# barbarov_guc_dagitim_karti.net
KiCad netlist of a schematic drawn in Altium Designer
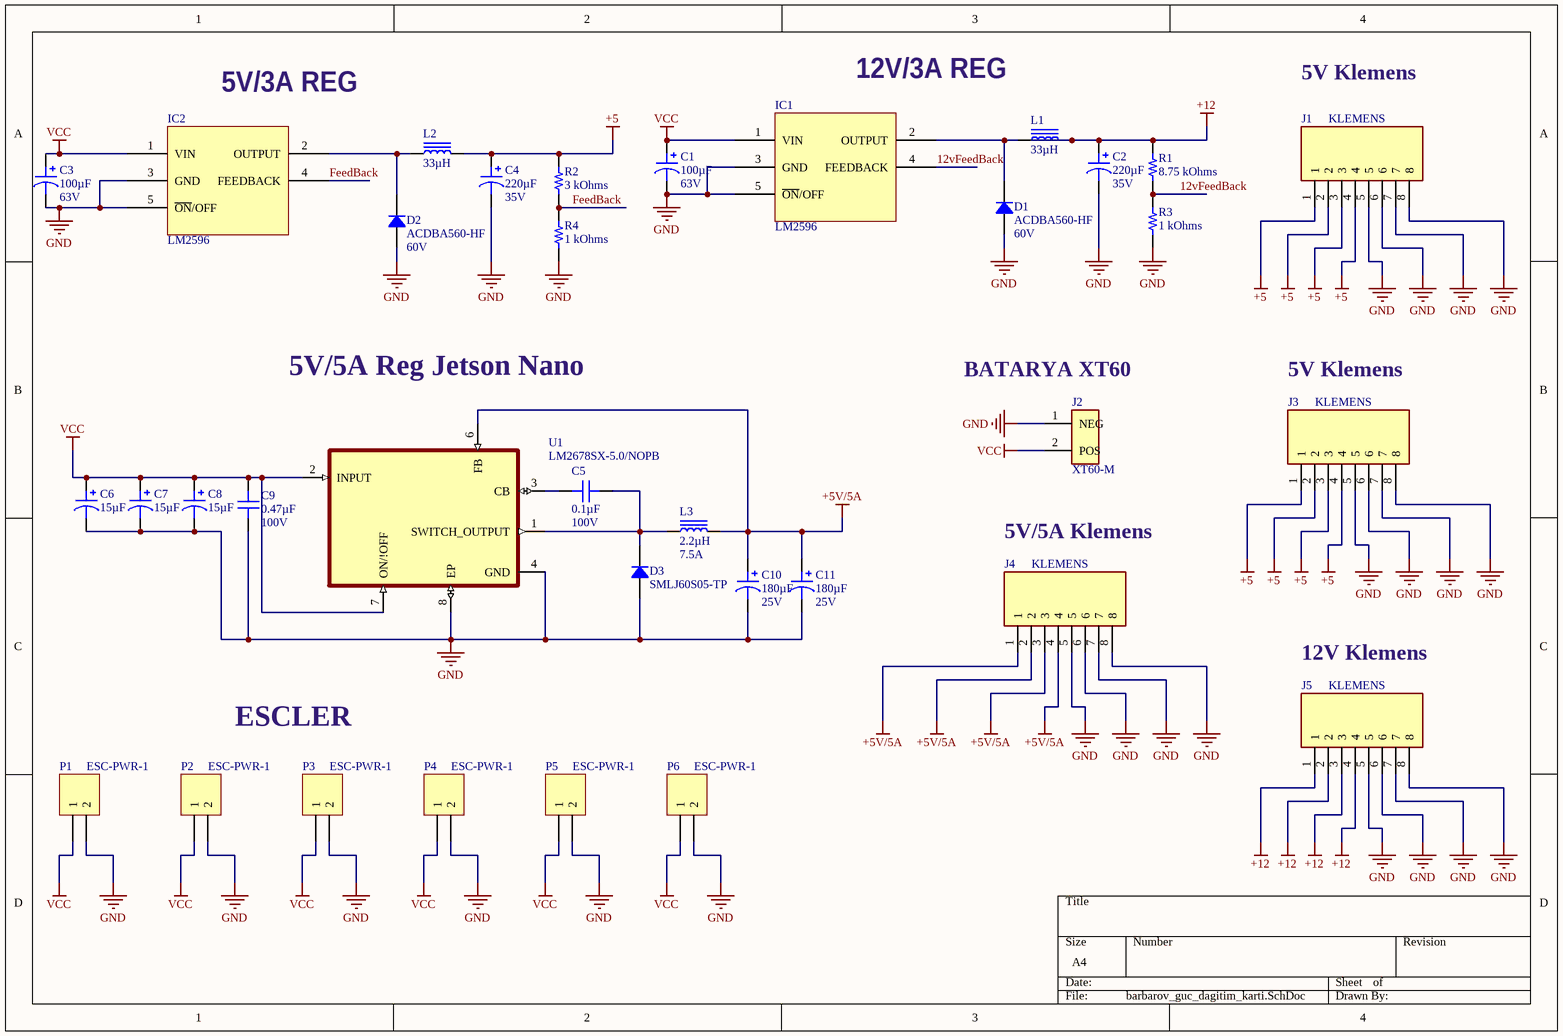
[diagram p0: barbarov_guc_dagitim_karti.SchDoc]

(export (version "E")
  (design (tool "Eeschema 10.0.6"))
  (components
    (comp (ref "C1")
      (value "100µF")
      (footprint "CAP TH ALUM ELEC D8.00mm S3.50mm H12.50mm")
      (description "CAP ALUM 100UF 20% 63V RADIAL")
      (fields
        (field (name "PART NUMBER") "ECA-1JM101")
        (field (name "MANUFACTURER") "Panasonic Electronic Components")
        (field (name "VOLTAGE - RATED") "63V")
      )
      (libsource (lib "Celestial Altium Library - altium_library") (part "Polarised Capacitor"))
    )
    (comp (ref "C2")
      (value "220µF")
      (footprint "CAP TH ALUM ELEC D8.00mm S3.50mm H12.50mm")
      (description "CAP ALUM 220UF 20% 35V RADIAL")
      (fields
        (field (name "PART NUMBER") "ECA-1VM221")
        (field (name "MANUFACTURER") "Panasonic Electronic Components")
        (field (name "VOLTAGE - RATED") "35V")
      )
      (libsource (lib "Celestial Altium Library - altium_library") (part "Polarised Capacitor"))
    )
    (comp (ref "C3")
      (value "100µF")
      (footprint "CAP TH ALUM ELEC D8.00mm S3.50mm H12.50mm")
      (description "CAP ALUM 100UF 20% 63V RADIAL")
      (fields
        (field (name "PART NUMBER") "ECA-1JM101")
        (field (name "MANUFACTURER") "Panasonic Electronic Components")
        (field (name "VOLTAGE - RATED") "63V")
      )
      (libsource (lib "Celestial Altium Library - altium_library") (part "Polarised Capacitor"))
    )
    (comp (ref "C4")
      (value "220µF")
      (footprint "CAP TH ALUM ELEC D8.00mm S3.50mm H12.50mm")
      (description "CAP ALUM 220UF 20% 35V RADIAL")
      (fields
        (field (name "PART NUMBER") "ECA-1VM221")
        (field (name "MANUFACTURER") "Panasonic Electronic Components")
        (field (name "VOLTAGE - RATED") "35V")
      )
      (libsource (lib "Celestial Altium Library - altium_library") (part "Polarised Capacitor"))
    )
    (comp (ref "C5")
      (value "0.1µF")
      (footprint "CAP 1206_3216 - 1.8MM")
      (description "CAP CER 0.47UF 100V X7R 1206")
      (fields
        (field (name "PART NUMBER") "C3216X7R2A474K160AE")
        (field (name "MANUFACTURER") "TDK Corporation")
        (field (name "VOLTAGE - RATED") "100V")
      )
      (libsource (lib "Celestial Altium Library - altium_library") (part "Capacitor"))
    )
    (comp (ref "C6")
      (value "15µF")
      (footprint "CAP TH ALUM ELEC D8.00mm S3.50mm H11.50mm")
      (description "CAP ALUM 15UF 20% 100V RADIAL")
      (fields (field (name "PART NUMBER") "UPW2A150MPD") (field (name "MANUFACTURER") "Nichicon"))
      (libsource (lib "Celestial Altium Library - altium_library") (part "Polarised Capacitor"))
    )
    (comp (ref "C7")
      (value "15µF")
      (footprint "CAP TH ALUM ELEC D8.00mm S3.50mm H11.50mm")
      (description "CAP ALUM 15UF 20% 100V RADIAL")
      (fields (field (name "PART NUMBER") "UPW2A150MPD") (field (name "MANUFACTURER") "Nichicon"))
      (libsource (lib "Celestial Altium Library - altium_library") (part "Polarised Capacitor"))
    )
    (comp (ref "C8")
      (value "15µF")
      (footprint "CAP TH ALUM ELEC D8.00mm S3.50mm H11.50mm")
      (description "CAP ALUM 15UF 20% 100V RADIAL")
      (fields (field (name "PART NUMBER") "UPW2A150MPD") (field (name "MANUFACTURER") "Nichicon"))
      (libsource (lib "Celestial Altium Library - altium_library") (part "Polarised Capacitor"))
    )
    (comp (ref "C9")
      (value "0.47µF")
      (footprint "CAP 1206_3216 - 1.8MM")
      (description "CAP CER 0.47UF 100V X7R 1206")
      (fields
        (field (name "PART NUMBER") "C3216X7R2A474K160AE")
        (field (name "MANUFACTURER") "TDK Corporation")
        (field (name "VOLTAGE - RATED") "100V")
      )
      (libsource (lib "Celestial Altium Library - altium_library") (part "Capacitor"))
    )
    (comp (ref "C10")
      (value "180µF")
      (footprint "CAP TH ALUM ELEC D8.00mm S3.50mm H13.00mm")
      (description "CAP ALUM 180UF 20% 25V THRU HOLE")
      (fields
        (field (name "PART NUMBER") "860080474009")
        (field (name "MANUFACTURER") "Würth Elektronik")
        (field (name "VOLTAGE - RATED") "25V")
      )
      (libsource (lib "Celestial Altium Library - altium_library") (part "Polarised Capacitor"))
    )
    (comp (ref "C11")
      (value "180µF")
      (footprint "CAP TH ALUM ELEC D8.00mm S3.50mm H13.00mm")
      (description "CAP ALUM 180UF 20% 25V THRU HOLE")
      (fields
        (field (name "PART NUMBER") "860080474009")
        (field (name "MANUFACTURER") "Würth Elektronik")
        (field (name "VOLTAGE - RATED") "25V")
      )
      (libsource (lib "Celestial Altium Library - altium_library") (part "Polarised Capacitor"))
    )
    (comp (ref "D1")
      (value "ACDBA560-HF")
      (footprint "DO214AC SMA")
      (description "DIODE SCHOTTKY 60V 5A DO214AC")
      (fields
        (field (name "MANUFACTURER") "Comchip Technology")
        (field (name "VOLTAGE - DC REVERSE (VR) (MAX)") "60V")
      )
      (libsource (lib "Celestial Altium Library - altium_library") (part "Diode"))
    )
    (comp (ref "D2")
      (value "ACDBA560-HF")
      (footprint "DO214AC SMA")
      (description "DIODE SCHOTTKY 60V 5A DO214AC")
      (fields
        (field (name "MANUFACTURER") "Comchip Technology")
        (field (name "VOLTAGE - DC REVERSE (VR) (MAX)") "60V")
      )
      (libsource (lib "Celestial Altium Library - altium_library") (part "Diode"))
    )
    (comp (ref "D3")
      (value "SMLJ60S05-TP")
      (footprint "DO214AB SMC")
      (description "DIODE GEN PURP 50V 6A DO214AB")
      (fields (field (name "MANUFACTURER") "Micro Commercial Co"))
      (libsource (lib "Celestial Altium Library - altium_library") (part "Diode"))
    )
    (comp (ref "IC1")
      (value "LM2596")
      (footprint "AltiumLive:D2PAK")
      (libsource (lib "AltiumLive") (part "LM2596"))
    )
    (comp (ref "IC2")
      (value "LM2596")
      (footprint "AltiumLive:D2PAK")
      (libsource (lib "AltiumLive") (part "LM2596"))
    )
    (comp (ref "J1")
      (value "KLEMENS")
      (footprint "TE_284512-8")
      (description "8 POS TERMI-BLOK HDR 900 POLAR")
      (fields (field (name "MF") "TE Connectivity") (field (name "MP") "284512-8"))
      (libsource (lib "SnapEDAsch") (part "284512-8"))
    )
    (comp (ref "J2")
      (value "XT60-M")
      (footprint "AMASS_XT60-M")
      (description "Plug; DC supply; XT60; male; PIN: 2; for cable; soldered; 30A; 500V")
      (fields (field (name "MF") "AMASS"))
      (libsource (lib "xt60sch") (part "XT60-M"))
    )
    (comp (ref "J3")
      (value "KLEMENS")
      (footprint "TE_284512-8")
      (description "8 POS TERMI-BLOK HDR 900 POLAR")
      (fields (field (name "MF") "TE Connectivity") (field (name "MP") "284512-8"))
      (libsource (lib "SnapEDAsch") (part "284512-8"))
    )
    (comp (ref "J4")
      (value "KLEMENS")
      (footprint "TE_284512-8")
      (description "8 POS TERMI-BLOK HDR 900 POLAR")
      (fields (field (name "MF") "TE Connectivity") (field (name "MP") "284512-8"))
      (libsource (lib "SnapEDAsch") (part "284512-8"))
    )
    (comp (ref "J5")
      (value "KLEMENS")
      (footprint "TE_284512-8")
      (description "8 POS TERMI-BLOK HDR 900 POLAR")
      (fields (field (name "MF") "TE Connectivity") (field (name "MP") "284512-8"))
      (libsource (lib "SnapEDAsch") (part "284512-8"))
    )
    (comp (ref "L1")
      (value "33µH")
      (footprint "BOURNS SRR1280")
      (description "FIXED IND 33UH 3.5A 57 MOHM SMD")
      (fields (field (name "PART NUMBER") "SRR1280-330M") (field (name "MANUFACTURER") "Bourns Inc."))
      (libsource (lib "Celestial Altium Library - altium_library") (part "Inductor"))
    )
    (comp (ref "L2")
      (value "33µH")
      (footprint "BOURNS SRR1280")
      (description "FIXED IND 33UH 3.5A 57 MOHM SMD")
      (fields (field (name "PART NUMBER") "SRR1280-330M") (field (name "MANUFACTURER") "Bourns Inc."))
      (libsource (lib "Celestial Altium Library - altium_library") (part "Inductor"))
    )
    (comp (ref "L3")
      (value "2.2µH")
      (footprint "WURTH 5040")
      (description "FIXED IND 2.2UH 7.5A 11.3 MOHM")
      (fields
        (field (name "PART NUMBER") "744316220")
        (field (name "CURRENT RATING (AMPS)") "7.5A")
        (field (name "MANUFACTURER") "Würth Elektronik")
      )
      (libsource (lib "Celestial Altium Library - altium_library") (part "Inductor"))
    )
    (comp (ref "P1")
      (value "ESC-PWR-1")
      (footprint "HDR1X2")
      (description "Header, 2-Pin")
      (fields (field (name "PUBLISHER") "Altium Limited"))
      (libsource (lib "Miscellaneous Connectors") (part "Header 2"))
    )
    (comp (ref "P2")
      (value "ESC-PWR-1")
      (footprint "HDR1X2")
      (description "Header, 2-Pin")
      (fields (field (name "PUBLISHER") "Altium Limited"))
      (libsource (lib "Miscellaneous Connectors") (part "Header 2"))
    )
    (comp (ref "P3")
      (value "ESC-PWR-1")
      (footprint "HDR1X2")
      (description "Header, 2-Pin")
      (fields (field (name "PUBLISHER") "Altium Limited"))
      (libsource (lib "Miscellaneous Connectors") (part "Header 2"))
    )
    (comp (ref "P4")
      (value "ESC-PWR-1")
      (footprint "HDR1X2")
      (description "Header, 2-Pin")
      (fields (field (name "PUBLISHER") "Altium Limited"))
      (libsource (lib "Miscellaneous Connectors") (part "Header 2"))
    )
    (comp (ref "P5")
      (value "ESC-PWR-1")
      (footprint "HDR1X2")
      (description "Header, 2-Pin")
      (fields (field (name "PUBLISHER") "Altium Limited"))
      (libsource (lib "Miscellaneous Connectors") (part "Header 2"))
    )
    (comp (ref "P6")
      (value "ESC-PWR-1")
      (footprint "HDR1X2")
      (description "Header, 2-Pin")
      (fields (field (name "PUBLISHER") "Altium Limited"))
      (libsource (lib "Miscellaneous Connectors") (part "Header 2"))
    )
    (comp (ref "R1")
      (value "8.75 kOhms")
      (footprint "RES 0805_2012")
      (description "RES 10K OHM 1% 1/4W 0805")
      (fields
        (field (name "PART NUMBER") "RNCP0805FTD10K0")
        (field (name "MANUFACTURER") "Stackpole Electronics Inc")
      )
      (libsource (lib "Celestial Altium Library - altium_library") (part "Resistor"))
    )
    (comp (ref "R2")
      (value "3 kOhms")
      (footprint "RES 0805_2012")
      (description "RES 10K OHM 1% 1/4W 0805")
      (fields
        (field (name "PART NUMBER") "RNCP0805FTD10K0")
        (field (name "MANUFACTURER") "Stackpole Electronics Inc")
      )
      (libsource (lib "Celestial Altium Library - altium_library") (part "Resistor"))
    )
    (comp (ref "R3")
      (value "1 kOhms")
      (footprint "RES 0805_2012")
      (description "CRGP 0805 4K7 1%")
      (fields
        (field (name "PART NUMBER") "CRGP0805F4K7")
        (field (name "MANUFACTURER") "TE Connectivity Passive Product")
      )
      (libsource (lib "Celestial Altium Library - altium_library") (part "Resistor"))
    )
    (comp (ref "R4")
      (value "1 kOhms")
      (footprint "RES 0805_2012")
      (description "CRGP 0805 4K7 1%")
      (fields
        (field (name "PART NUMBER") "CRGP0805F4K7")
        (field (name "MANUFACTURER") "TE Connectivity Passive Product")
      )
      (libsource (lib "Celestial Altium Library - altium_library") (part "Resistor"))
    )
    (comp (ref "U1")
      (value "LM2678SX-5.0/NOPB")
      (footprint "TO127P1435X464-8N")
      (description "8V to 40V, 5A SIMPLE SWITCHER buck converter with high efficiency 7-DDPAK/TO-263 -40 to 125")
      (fields
        (field (name "MF") "Texas Instruments")
        (field (name "DIGI-KEY_PART_NUMBER") "LM2678SX-5.0/NOPBCT-ND")
      )
      (libsource (lib "LM2678SX-5.0_NOPB") (part "LM2678SX-5.0/NOPB"))
    )
  )
  (nets
    (net (code "1") (name "+5") (class "Default")
      (node (ref "C4") (pin "1") (pinfunction "1_1") (pintype "passive"))
      (node (ref "J1") (pin "1") (pinfunction "1_1") (pintype "passive"))
      (node (ref "J1") (pin "2") (pinfunction "2_2") (pintype "passive"))
      (node (ref "J1") (pin "3") (pinfunction "3_3") (pintype "passive"))
      (node (ref "J1") (pin "4") (pinfunction "4_4") (pintype "passive"))
      (node (ref "J3") (pin "1") (pinfunction "1_1") (pintype "passive"))
      (node (ref "J3") (pin "2") (pinfunction "2_2") (pintype "passive"))
      (node (ref "J3") (pin "3") (pinfunction "3_3") (pintype "passive"))
      (node (ref "J3") (pin "4") (pinfunction "4_4") (pintype "passive"))
      (node (ref "L2") (pin "2") (pinfunction "2_2") (pintype "passive"))
      (node (ref "R2") (pin "2") (pinfunction "2_2") (pintype "passive"))
    )
    (net (code "2") (name "+5V{slash}5A") (class "Default")
      (node (ref "C10") (pin "1") (pinfunction "1_1") (pintype "passive"))
      (node (ref "C11") (pin "1") (pinfunction "1_1") (pintype "passive"))
      (node (ref "J4") (pin "1") (pinfunction "1_1") (pintype "passive"))
      (node (ref "J4") (pin "2") (pinfunction "2_2") (pintype "passive"))
      (node (ref "J4") (pin "3") (pinfunction "3_3") (pintype "passive"))
      (node (ref "J4") (pin "4") (pinfunction "4_4") (pintype "passive"))
      (node (ref "L3") (pin "2") (pinfunction "2_2") (pintype "passive"))
      (node (ref "U1") (pin "6") (pinfunction "FB_6") (pintype "input"))
    )
    (net (code "3") (name "+12") (class "Default")
      (node (ref "C2") (pin "1") (pinfunction "1_1") (pintype "passive"))
      (node (ref "J5") (pin "1") (pinfunction "1_1") (pintype "passive"))
      (node (ref "J5") (pin "2") (pinfunction "2_2") (pintype "passive"))
      (node (ref "J5") (pin "3") (pinfunction "3_3") (pintype "passive"))
      (node (ref "J5") (pin "4") (pinfunction "4_4") (pintype "passive"))
      (node (ref "L1") (pin "2") (pinfunction "2_2") (pintype "passive"))
      (node (ref "R1") (pin "2") (pinfunction "2_2") (pintype "passive"))
    )
    (net (code "4") (name "/12vFeedBack") (class "Default")
      (node (ref "IC1") (pin "4") (pinfunction "FEEDBACK_4") (pintype "passive"))
      (node (ref "R1") (pin "1") (pinfunction "1_1") (pintype "passive"))
      (node (ref "R3") (pin "2") (pinfunction "2_2") (pintype "passive"))
    )
    (net (code "5") (name "/FeedBack") (class "Default")
      (node (ref "IC2") (pin "4") (pinfunction "FEEDBACK_4") (pintype "passive"))
      (node (ref "R2") (pin "1") (pinfunction "1_1") (pintype "passive"))
      (node (ref "R4") (pin "2") (pinfunction "2_2") (pintype "passive"))
    )
    (net (code "6") (name "GND") (class "Default")
      (node (ref "C1") (pin "2") (pinfunction "2_2") (pintype "passive"))
      (node (ref "C10") (pin "2") (pinfunction "2_2") (pintype "passive"))
      (node (ref "C11") (pin "2") (pinfunction "2_2") (pintype "passive"))
      (node (ref "C2") (pin "2") (pinfunction "2_2") (pintype "passive"))
      (node (ref "C3") (pin "2") (pinfunction "2_2") (pintype "passive"))
      (node (ref "C4") (pin "2") (pinfunction "2_2") (pintype "passive"))
      (node (ref "C6") (pin "2") (pinfunction "2_2") (pintype "passive"))
      (node (ref "C7") (pin "2") (pinfunction "2_2") (pintype "passive"))
      (node (ref "C8") (pin "2") (pinfunction "2_2") (pintype "passive"))
      (node (ref "C9") (pin "1") (pinfunction "1_1") (pintype "passive"))
      (node (ref "D1") (pin "1") (pinfunction "1_1") (pintype "passive"))
      (node (ref "D2") (pin "1") (pinfunction "1_1") (pintype "passive"))
      (node (ref "D3") (pin "1") (pinfunction "1_1") (pintype "passive"))
      (node (ref "IC1") (pin "3") (pinfunction "GND_3") (pintype "passive"))
      (node (ref "IC1") (pin "5") (pinfunction "~{ON}/OFF_5") (pintype "passive"))
      (node (ref "IC2") (pin "3") (pinfunction "GND_3") (pintype "passive"))
      (node (ref "IC2") (pin "5") (pinfunction "~{ON}/OFF_5") (pintype "passive"))
      (node (ref "J1") (pin "5") (pinfunction "5_5") (pintype "passive"))
      (node (ref "J1") (pin "6") (pinfunction "6_6") (pintype "passive"))
      (node (ref "J1") (pin "7") (pinfunction "7_7") (pintype "passive"))
      (node (ref "J1") (pin "8") (pinfunction "8_8") (pintype "passive"))
      (node (ref "J2") (pin "1") (pinfunction "NEG_1") (pintype "passive"))
      (node (ref "J3") (pin "5") (pinfunction "5_5") (pintype "passive"))
      (node (ref "J3") (pin "6") (pinfunction "6_6") (pintype "passive"))
      (node (ref "J3") (pin "7") (pinfunction "7_7") (pintype "passive"))
      (node (ref "J3") (pin "8") (pinfunction "8_8") (pintype "passive"))
      (node (ref "J4") (pin "5") (pinfunction "5_5") (pintype "passive"))
      (node (ref "J4") (pin "6") (pinfunction "6_6") (pintype "passive"))
      (node (ref "J4") (pin "7") (pinfunction "7_7") (pintype "passive"))
      (node (ref "J4") (pin "8") (pinfunction "8_8") (pintype "passive"))
      (node (ref "J5") (pin "5") (pinfunction "5_5") (pintype "passive"))
      (node (ref "J5") (pin "6") (pinfunction "6_6") (pintype "passive"))
      (node (ref "J5") (pin "7") (pinfunction "7_7") (pintype "passive"))
      (node (ref "J5") (pin "8") (pinfunction "8_8") (pintype "passive"))
      (node (ref "P1") (pin "2") (pinfunction "2_2") (pintype "passive"))
      (node (ref "P2") (pin "2") (pinfunction "2_2") (pintype "passive"))
      (node (ref "P3") (pin "2") (pinfunction "2_2") (pintype "passive"))
      (node (ref "P4") (pin "2") (pinfunction "2_2") (pintype "passive"))
      (node (ref "P5") (pin "2") (pinfunction "2_2") (pintype "passive"))
      (node (ref "P6") (pin "2") (pinfunction "2_2") (pintype "passive"))
      (node (ref "R3") (pin "1") (pinfunction "1_1") (pintype "passive"))
      (node (ref "R4") (pin "1") (pinfunction "1_1") (pintype "passive"))
      (node (ref "U1") (pin "4") (pinfunction "GND_4") (pintype "power_in"))
      (node (ref "U1") (pin "8") (pinfunction "EP_8") (pintype "bidirectional"))
    )
    (net (code "7") (name "Net-(IC1-OUTPUT)") (class "Default")
      (node (ref "D1") (pin "2") (pinfunction "2_2") (pintype "passive"))
      (node (ref "IC1") (pin "2") (pinfunction "OUTPUT_2") (pintype "passive"))
      (node (ref "L1") (pin "1") (pinfunction "1_1") (pintype "passive"))
    )
    (net (code "8") (name "Net-(IC2-OUTPUT)") (class "Default")
      (node (ref "D2") (pin "2") (pinfunction "2_2") (pintype "passive"))
      (node (ref "IC2") (pin "2") (pinfunction "OUTPUT_2") (pintype "passive"))
      (node (ref "L2") (pin "1") (pinfunction "1_1") (pintype "passive"))
    )
    (net (code "9") (name "Net-(U1-CB)") (class "Default")
      (node (ref "C5") (pin "2") (pinfunction "2_2") (pintype "passive"))
      (node (ref "U1") (pin "3") (pinfunction "CB_3") (pintype "bidirectional"))
    )
    (net (code "10") (name "Net-(U1-SWITCH_OUTPUT)") (class "Default")
      (node (ref "C5") (pin "1") (pinfunction "1_1") (pintype "passive"))
      (node (ref "D3") (pin "2") (pinfunction "2_2") (pintype "passive"))
      (node (ref "L3") (pin "1") (pinfunction "1_1") (pintype "passive"))
      (node (ref "U1") (pin "1") (pinfunction "SWITCH_OUTPUT_1") (pintype "output"))
    )
    (net (code "11") (name "VCC") (class "Default")
      (node (ref "C1") (pin "1") (pinfunction "1_1") (pintype "passive"))
      (node (ref "C3") (pin "1") (pinfunction "1_1") (pintype "passive"))
      (node (ref "C6") (pin "1") (pinfunction "1_1") (pintype "passive"))
      (node (ref "C7") (pin "1") (pinfunction "1_1") (pintype "passive"))
      (node (ref "C8") (pin "1") (pinfunction "1_1") (pintype "passive"))
      (node (ref "C9") (pin "2") (pinfunction "2_2") (pintype "passive"))
      (node (ref "IC1") (pin "1") (pinfunction "VIN_1") (pintype "passive"))
      (node (ref "IC2") (pin "1") (pinfunction "VIN_1") (pintype "passive"))
      (node (ref "J2") (pin "2") (pinfunction "POS_2") (pintype "passive"))
      (node (ref "P1") (pin "1") (pinfunction "1_1") (pintype "passive"))
      (node (ref "P2") (pin "1") (pinfunction "1_1") (pintype "passive"))
      (node (ref "P3") (pin "1") (pinfunction "1_1") (pintype "passive"))
      (node (ref "P4") (pin "1") (pinfunction "1_1") (pintype "passive"))
      (node (ref "P5") (pin "1") (pinfunction "1_1") (pintype "passive"))
      (node (ref "P6") (pin "1") (pinfunction "1_1") (pintype "passive"))
      (node (ref "U1") (pin "2") (pinfunction "INPUT_2") (pintype "input"))
      (node (ref "U1") (pin "7") (pinfunction "ON/!OFF_7") (pintype "input"))
    )
  )
)
